# fresh_air_control.net
KiCad netlist of a schematic drawn in EAGLE
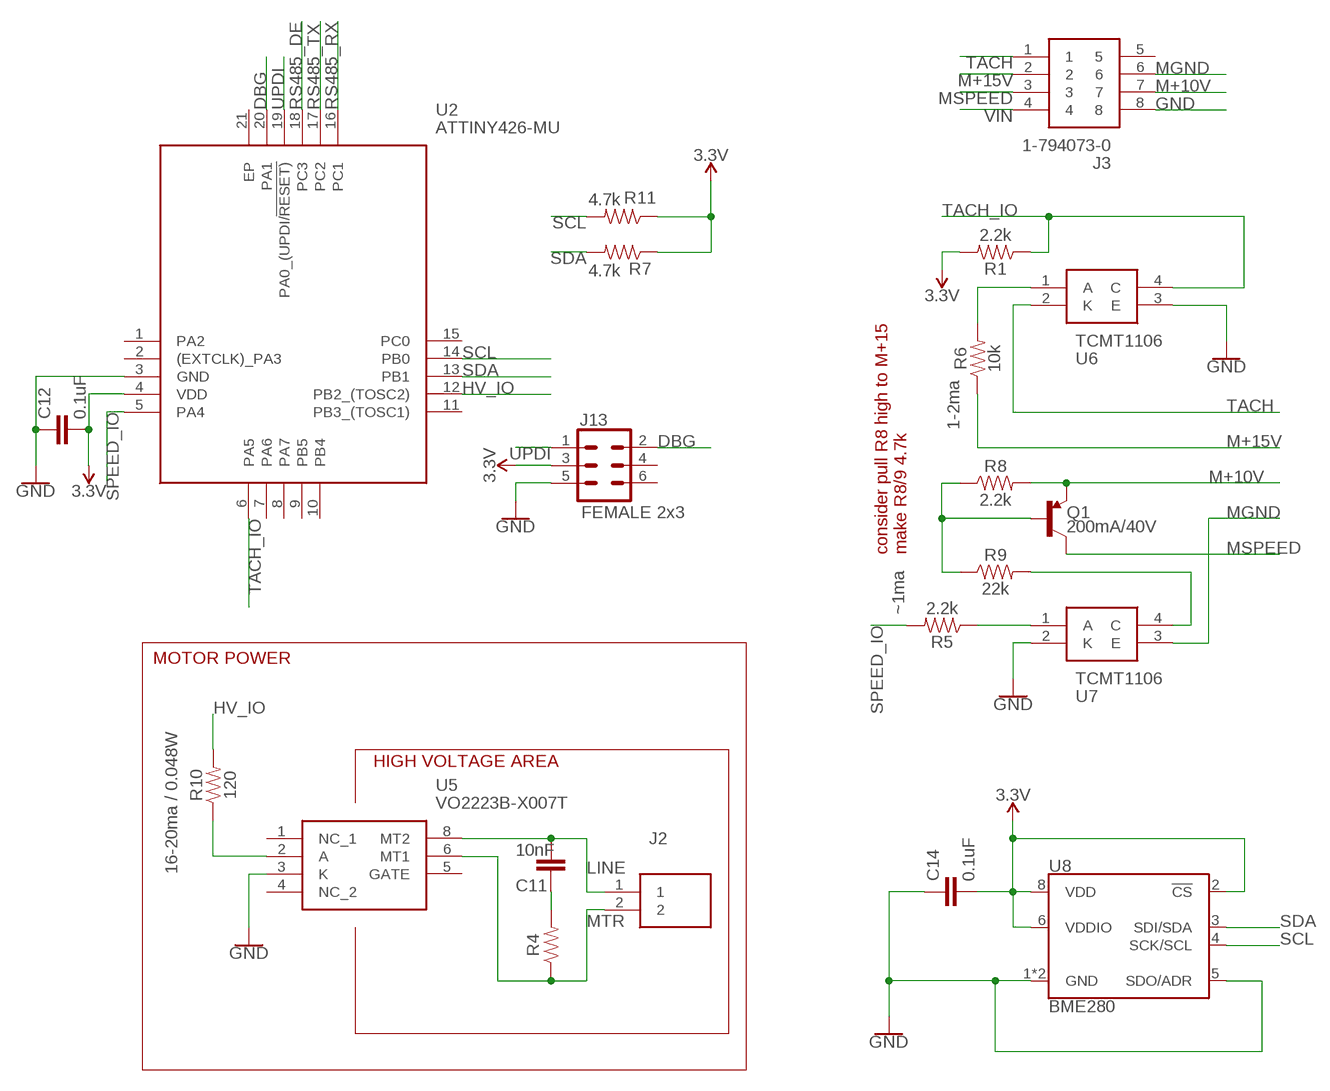
[diagram p0: schematic, sheet 1]
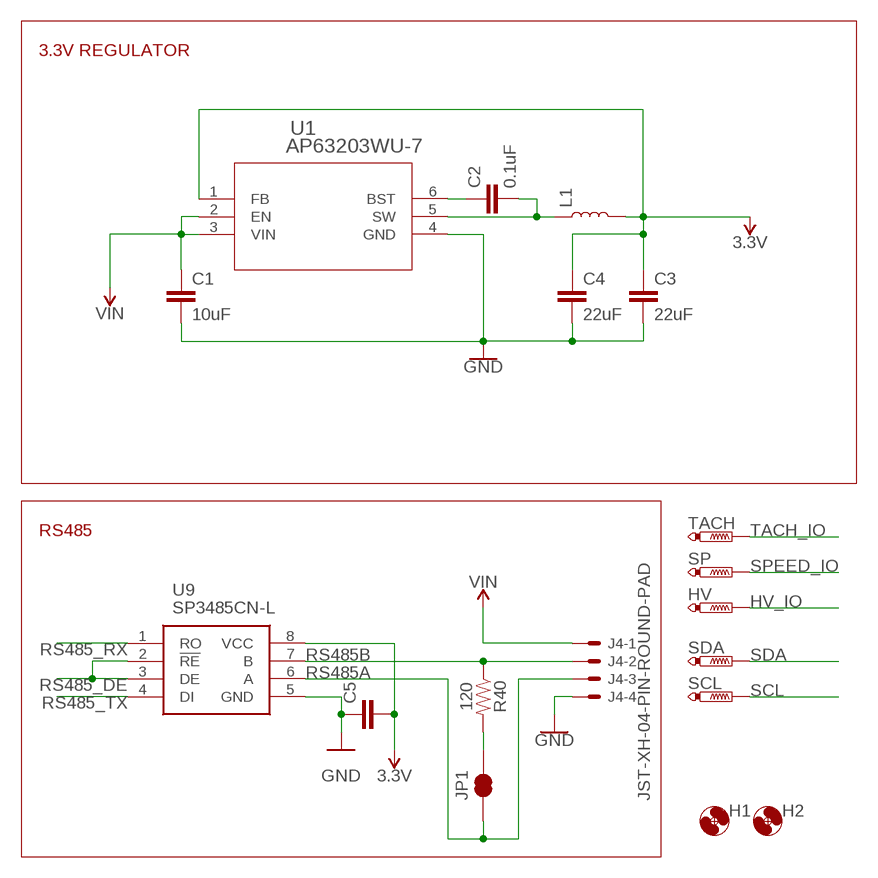
[diagram p1: schematic, sheet 2]

(export (version "E")
  (design (tool "Eeschema 10.0.6"))
  (components
    (comp (ref "C11")
      (value "10nF")
      (footprint "eagle-import:0805")
      (libsource (lib "eagle-import") (part "10NF-0805-400V-20%"))
    )
    (comp (ref "C12")
      (value "0.1uF")
      (footprint "eagle-import:0603")
      (libsource (lib "eagle-import") (part "0.1UF-0603-25V-5%"))
    )
    (comp (ref "C14")
      (value "0.1uF")
      (footprint "eagle-import:0603")
      (libsource (lib "eagle-import") (part "0.1UF-0603-25V-5%"))
    )
    (comp (ref "J2")
      (value "1-770166-0")
      (footprint "eagle-import:17701660")
      (fields (field (name "MOUSER_PART_NUMBER") "571-1-770166-0"))
      (libsource (lib "eagle-import") (part "1-770166-0"))
    )
    (comp (ref "J3")
      (value "1-794073-0")
      (footprint "eagle-import:17940730")
      (fields (field (name "MOUSER_PART_NUMBER") "571-1-794073-0"))
      (libsource (lib "eagle-import") (part "1-794073-0"))
    )
    (comp (ref "J13")
      (value "FEMALE 2x3")
      (footprint "eagle-import:2X3")
      (libsource (lib "eagle-import") (part "CONN_03X2FEMALE"))
    )
    (comp (ref "Q1")
      (value "200mA/40V")
      (footprint "eagle-import:SOT23-3")
      (libsource (lib "eagle-import") (part "TRANS_PNP-PMBT3906|MMBT3906L"))
    )
    (comp (ref "R1")
      (value "2.2k")
      (footprint "eagle-import:0603")
      (libsource (lib "eagle-import") (part "2.2KOHM-0603-1/10W-1%"))
    )
    (comp (ref "R4")
      (value "100")
      (footprint "eagle-import:0805")
      (libsource (lib "eagle-import") (part "100OHM-0805-1/10W-5%-400V"))
    )
    (comp (ref "R5")
      (value "2.2k")
      (footprint "eagle-import:0603")
      (libsource (lib "eagle-import") (part "2.2KOHM-0603-1/10W-1%"))
    )
    (comp (ref "R6")
      (value "10k")
      (footprint "eagle-import:0603")
      (libsource (lib "eagle-import") (part "10KOHM-0603-1/10W-1%"))
    )
    (comp (ref "R7")
      (value "4.7k")
      (footprint "eagle-import:0603")
      (libsource (lib "eagle-import") (part "4.7KOHM-0603-1/10W-1%"))
    )
    (comp (ref "R8")
      (value "2.2k")
      (footprint "eagle-import:0603")
      (libsource (lib "eagle-import") (part "2.2KOHM-0603-1/10W-1%"))
    )
    (comp (ref "R9")
      (value "22k")
      (footprint "eagle-import:0603")
      (libsource (lib "eagle-import") (part "22KOHM-0603-1/10W-1%"))
    )
    (comp (ref "R10")
      (value "120")
      (footprint "eagle-import:0603")
      (libsource (lib "eagle-import") (part "120OHM-0603-1/10W-5%"))
    )
    (comp (ref "R11")
      (value "4.7k")
      (footprint "eagle-import:0603")
      (libsource (lib "eagle-import") (part "4.7KOHM-0603-1/10W-1%"))
    )
    (comp (ref "U2")
      (value "ATTINY426-MU")
      (footprint "eagle-import:QFN40P300X300X90-21N")
      (fields (field (name "MOUSER_PART_NUMBER") "579-ATTINY426-MU"))
      (libsource (lib "eagle-import") (part "ATTINY426-MU"))
    )
    (comp (ref "U5")
      (value "VO2223B-X007T")
      (footprint "eagle-import:VO2223BX007T")
      (fields (field (name "MOUSER_PART_NUMBER") "78-VO2223B-X007T"))
      (libsource (lib "eagle-import") (part "VO2223B-X007T"))
    )
    (comp (ref "U6")
      (value "TCMT1106")
      (footprint "eagle-import:SOIC127P700X230-4N")
      (fields (field (name "MOUSER_PART_NUMBER") "782-TCMT1106"))
      (libsource (lib "eagle-import") (part "TCMT1106"))
    )
    (comp (ref "U7")
      (value "TCMT1106")
      (footprint "eagle-import:SOIC127P700X230-4N")
      (fields (field (name "MOUSER_PART_NUMBER") "782-TCMT1106"))
      (libsource (lib "eagle-import") (part "TCMT1106"))
    )
    (comp (ref "U8")
      (value "BME280")
      (footprint "eagle-import:LGA-8-2.5X2.5")
      (libsource (lib "eagle-import") (part "BME280"))
    )
    (comp (ref "C1")
      (value "10uF")
      (footprint "eagle-import:1206")
      (libsource (lib "eagle-import") (part "10UF-1206-6.3V-20%"))
    )
    (comp (ref "C2")
      (value "0.1uF")
      (footprint "eagle-import:0603")
      (libsource (lib "eagle-import") (part "0.1UF-0603-25V-5%"))
    )
    (comp (ref "C3")
      (value "22uF")
      (footprint "eagle-import:0805")
      (libsource (lib "eagle-import") (part "22UF-0805-6.3V-20%"))
    )
    (comp (ref "C4")
      (value "22uF")
      (footprint "eagle-import:0805")
      (libsource (lib "eagle-import") (part "22UF-0805-6.3V-20%"))
    )
    (comp (ref "C5")
      (value "0.1uF")
      (footprint "eagle-import:0603")
      (libsource (lib "eagle-import") (part "0.1UF-0603-25V-5%"))
    )
    (comp (ref "H1")
      (value "MOUNT-HOLE3.3")
      (footprint "eagle-import:3,3")
      (libsource (lib "eagle-import") (part "MOUNT-HOLE3.3"))
    )
    (comp (ref "H2")
      (value "MOUNT-HOLE3.3")
      (footprint "eagle-import:3,3")
      (libsource (lib "eagle-import") (part "MOUNT-HOLE3.3"))
    )
    (comp (ref "HV")
      (value "PTR1B1,27")
      (footprint "eagle-import:B1,27")
      (libsource (lib "eagle-import") (part "PTR1B1,27"))
    )
    (comp (ref "J4")
      (value "JST-XH-04-PIN-ROUND-PAD")
      (footprint "eagle-import:JST-XH-04-PACKAGE-ROUND-PAD")
      (libsource (lib "eagle-import") (part "JST-XH-04-PIN-ROUND-PAD"))
    )
    (comp (ref "JP1")
      (value "JUMPER-SMT_2_NC_TRACE_NO-SILK")
      (footprint "eagle-import:SMT-JUMPER_2_NC_TRACE_NO-SILK")
      (libsource (lib "eagle-import") (part "JUMPER-SMT_2_NC_TRACE_NO-SILK"))
    )
    (comp (ref "L1")
      (value "4.7μH_SHIELDED_INDUCTOR")
      (footprint "eagle-import:1008(2520)")
      (libsource (lib "eagle-import") (part "4.7μH_SHIELDED_INDUCTOR"))
    )
    (comp (ref "R40")
      (value "120")
      (footprint "eagle-import:0603")
      (libsource (lib "eagle-import") (part "120OHM-0603-1/10W-5%"))
    )
    (comp (ref "SCL")
      (value "PTR1B1,27")
      (footprint "eagle-import:B1,27")
      (libsource (lib "eagle-import") (part "PTR1B1,27"))
    )
    (comp (ref "SDA")
      (value "PTR1B1,27")
      (footprint "eagle-import:B1,27")
      (libsource (lib "eagle-import") (part "PTR1B1,27"))
    )
    (comp (ref "SP")
      (value "PTR1B1,27")
      (footprint "eagle-import:B1,27")
      (libsource (lib "eagle-import") (part "PTR1B1,27"))
    )
    (comp (ref "TACH")
      (value "PTR1B1,27")
      (footprint "eagle-import:B1,27")
      (libsource (lib "eagle-import") (part "PTR1B1,27"))
    )
    (comp (ref "U1")
      (value "AP63203WU-7")
      (footprint "eagle-import:SOIC_05WU-7_DIO")
      (fields (field (name "COPYRIGHT") "Copyright (C) 2023 Ultra Librarian. All rights reserved."))
      (libsource (lib "eagle-import") (part "AP63203WU-7"))
    )
    (comp (ref "U9")
      (value "SP3485CN-L")
      (footprint "eagle-import:SOIC127P600X175-8N")
      (fields (field (name "MOUSER_PART_NUMBER") "701-SP3485CN-L"))
      (libsource (lib "eagle-import") (part "SP3485CN-L"))
    )
  )
  (nets
    (net (code "1") (name "3.3V") (class "Default")
      (node (ref "C12") (pin "2") (pinfunction "2_2") (pintype "passive"))
      (node (ref "C14") (pin "2") (pinfunction "2_2") (pintype "passive"))
      (node (ref "C3") (pin "1") (pinfunction "1_1") (pintype "passive"))
      (node (ref "C4") (pin "1") (pinfunction "1_1") (pintype "passive"))
      (node (ref "C5") (pin "2") (pinfunction "2_2") (pintype "passive"))
      (node (ref "J13") (pin "3") (pinfunction "3_3") (pintype "bidirectional"))
      (node (ref "L1") (pin "2") (pinfunction "2_2") (pintype "passive"))
      (node (ref "R1") (pin "2") (pinfunction "2_2") (pintype "passive"))
      (node (ref "R11") (pin "1") (pinfunction "1_1") (pintype "passive"))
      (node (ref "R7") (pin "1") (pinfunction "1_1") (pintype "passive"))
      (node (ref "U1") (pin "1") (pinfunction "FB_1") (pintype "passive"))
      (node (ref "U2") (pin "4") (pinfunction "VDD_4") (pintype "bidirectional"))
      (node (ref "U8") (pin "2") (pinfunction "~{CS}_2") (pintype "bidirectional"))
      (node (ref "U8") (pin "6") (pinfunction "VDDIO_6") (pintype "bidirectional"))
      (node (ref "U8") (pin "8") (pinfunction "VDD_8") (pintype "bidirectional"))
      (node (ref "U9") (pin "8") (pinfunction "VCC_8") (pintype "bidirectional"))
    )
    (net (code "2") (name "DBG") (class "Default")
      (node (ref "J13") (pin "2") (pinfunction "2_2") (pintype "bidirectional"))
      (node (ref "U2") (pin "20") (pinfunction "PA1_20") (pintype "bidirectional"))
    )
    (net (code "3") (name "GND") (class "Default")
      (node (ref "C1") (pin "2") (pinfunction "2_2") (pintype "passive"))
      (node (ref "C12") (pin "1") (pinfunction "1_1") (pintype "passive"))
      (node (ref "C14") (pin "1") (pinfunction "1_1") (pintype "passive"))
      (node (ref "C3") (pin "2") (pinfunction "2_2") (pintype "passive"))
      (node (ref "C4") (pin "2") (pinfunction "2_2") (pintype "passive"))
      (node (ref "C5") (pin "1") (pinfunction "1_1") (pintype "passive"))
      (node (ref "J13") (pin "5") (pinfunction "5_5") (pintype "bidirectional"))
      (node (ref "J3") (pin "8") (pinfunction "8_8") (pintype "bidirectional"))
      (node (ref "J4") (pin "4") (pinfunction "S_4") (pintype "passive"))
      (node (ref "U1") (pin "4") (pinfunction "GND_4") (pintype "passive"))
      (node (ref "U2") (pin "3") (pinfunction "GND_3") (pintype "bidirectional"))
      (node (ref "U5") (pin "3") (pinfunction "K_3") (pintype "bidirectional"))
      (node (ref "U6") (pin "3") (pinfunction "E_3") (pintype "bidirectional"))
      (node (ref "U7") (pin "2") (pinfunction "K_2") (pintype "bidirectional"))
      (node (ref "U8") (pin "1") (pinfunction "GND_1") (pintype "bidirectional"))
      (node (ref "U8") (pin "5") (pinfunction "SDO/ADR_5") (pintype "bidirectional"))
      (node (ref "U8") (pin "7") (pinfunction "GND_7") (pintype "bidirectional"))
      (node (ref "U9") (pin "5") (pinfunction "GND_5") (pintype "bidirectional"))
    )
    (net (code "4") (name "HV_IO") (class "Default")
      (node (ref "HV") (pin "TP") (pinfunction "TP_TP") (pintype "input"))
      (node (ref "R10") (pin "2") (pinfunction "2_2") (pintype "passive"))
      (node (ref "U2") (pin "12") (pinfunction "PB2_(TOSC2)_12") (pintype "bidirectional"))
    )
    (net (code "5") (name "LINE") (class "Default")
      (node (ref "C11") (pin "1") (pinfunction "1_1") (pintype "passive"))
      (node (ref "J2") (pin "1") (pinfunction "1_1") (pintype "bidirectional"))
      (node (ref "U5") (pin "8") (pinfunction "MT2_8") (pintype "bidirectional"))
    )
    (net (code "6") (name "M+10V") (class "Default")
      (node (ref "J3") (pin "7") (pinfunction "7_7") (pintype "bidirectional"))
      (node (ref "Q1") (pin "2") (pinfunction "E_2") (pintype "passive"))
      (node (ref "R8") (pin "2") (pinfunction "2_2") (pintype "passive"))
    )
    (net (code "7") (name "M+15V") (class "Default")
      (node (ref "J3") (pin "2") (pinfunction "2_2") (pintype "bidirectional"))
      (node (ref "R6") (pin "1") (pinfunction "1_1") (pintype "passive"))
    )
    (net (code "8") (name "MGND") (class "Default")
      (node (ref "J3") (pin "6") (pinfunction "6_6") (pintype "bidirectional"))
      (node (ref "U7") (pin "3") (pinfunction "E_3") (pintype "bidirectional"))
    )
    (net (code "9") (name "MSPEED") (class "Default")
      (node (ref "J3") (pin "3") (pinfunction "3_3") (pintype "bidirectional"))
      (node (ref "Q1") (pin "3") (pinfunction "C_3") (pintype "passive"))
    )
    (net (code "10") (name "MTR") (class "Default")
      (node (ref "J2") (pin "2") (pinfunction "2_2") (pintype "bidirectional"))
      (node (ref "R4") (pin "1") (pinfunction "1_1") (pintype "passive"))
      (node (ref "U5") (pin "6") (pinfunction "MT1_6") (pintype "bidirectional"))
    )
    (net (code "11") (name "Net-(C11-Pad2)") (class "Default")
      (node (ref "C11") (pin "2") (pinfunction "2_2") (pintype "passive"))
      (node (ref "R4") (pin "2") (pinfunction "2_2") (pintype "passive"))
    )
    (net (code "12") (name "Net-(JP1-Pad2)") (class "Default")
      (node (ref "JP1") (pin "2") (pinfunction "2_2") (pintype "passive"))
      (node (ref "R40") (pin "2") (pinfunction "2_2") (pintype "passive"))
    )
    (net (code "13") (name "Net-(Q1-B)") (class "Default")
      (node (ref "Q1") (pin "1") (pinfunction "B_1") (pintype "passive"))
      (node (ref "R8") (pin "1") (pinfunction "1_1") (pintype "passive"))
      (node (ref "R9") (pin "1") (pinfunction "1_1") (pintype "passive"))
    )
    (net (code "14") (name "Net-(U1-BST)") (class "Default")
      (node (ref "C2") (pin "1") (pinfunction "1_1") (pintype "passive"))
      (node (ref "U1") (pin "6") (pinfunction "BST_6") (pintype "passive"))
    )
    (net (code "15") (name "Net-(U1-SW)") (class "Default")
      (node (ref "C2") (pin "2") (pinfunction "2_2") (pintype "passive"))
      (node (ref "L1") (pin "1") (pinfunction "1_1") (pintype "passive"))
      (node (ref "U1") (pin "5") (pinfunction "SW_5") (pintype "passive"))
    )
    (net (code "16") (name "Net-(U5-A)") (class "Default")
      (node (ref "R10") (pin "1") (pinfunction "1_1") (pintype "passive"))
      (node (ref "U5") (pin "2") (pinfunction "A_2") (pintype "bidirectional"))
    )
    (net (code "17") (name "Net-(U6-A)") (class "Default")
      (node (ref "R6") (pin "2") (pinfunction "2_2") (pintype "passive"))
      (node (ref "U6") (pin "1") (pinfunction "A_1") (pintype "bidirectional"))
    )
    (net (code "18") (name "Net-(U7-A)") (class "Default")
      (node (ref "R5") (pin "1") (pinfunction "1_1") (pintype "passive"))
      (node (ref "U7") (pin "1") (pinfunction "A_1") (pintype "bidirectional"))
    )
    (net (code "19") (name "Net-(U7-C)") (class "Default")
      (node (ref "R9") (pin "2") (pinfunction "2_2") (pintype "passive"))
      (node (ref "U7") (pin "4") (pinfunction "C_4") (pintype "bidirectional"))
    )
    (net (code "20") (name "RS485A") (class "Default")
      (node (ref "J4") (pin "3") (pinfunction "S_3") (pintype "passive"))
      (node (ref "JP1") (pin "1") (pinfunction "1_1") (pintype "passive"))
      (node (ref "U9") (pin "6") (pinfunction "A_6") (pintype "bidirectional"))
    )
    (net (code "21") (name "RS485B") (class "Default")
      (node (ref "J4") (pin "2") (pinfunction "S_2") (pintype "passive"))
      (node (ref "R40") (pin "1") (pinfunction "1_1") (pintype "passive"))
      (node (ref "U9") (pin "7") (pinfunction "B_7") (pintype "bidirectional"))
    )
    (net (code "22") (name "RS485_DE") (class "Default")
      (node (ref "U2") (pin "18") (pinfunction "PC3_18") (pintype "bidirectional"))
      (node (ref "U9") (pin "2") (pinfunction "~{RE}_2") (pintype "bidirectional"))
      (node (ref "U9") (pin "3") (pinfunction "DE_3") (pintype "bidirectional"))
    )
    (net (code "23") (name "RS485_RX") (class "Default")
      (node (ref "U2") (pin "16") (pinfunction "PC1_16") (pintype "bidirectional"))
      (node (ref "U9") (pin "1") (pinfunction "RO_1") (pintype "bidirectional"))
    )
    (net (code "24") (name "RS485_TX") (class "Default")
      (node (ref "U2") (pin "17") (pinfunction "PC2_17") (pintype "bidirectional"))
      (node (ref "U9") (pin "4") (pinfunction "DI_4") (pintype "bidirectional"))
    )
    (net (code "25") (name "SCL") (class "Default")
      (node (ref "R11") (pin "2") (pinfunction "2_2") (pintype "passive"))
      (node (ref "SCL") (pin "TP") (pinfunction "TP_TP") (pintype "input"))
      (node (ref "U2") (pin "14") (pinfunction "PB0_14") (pintype "bidirectional"))
      (node (ref "U8") (pin "4") (pinfunction "SCK/SCL_4") (pintype "bidirectional"))
    )
    (net (code "26") (name "SDA") (class "Default")
      (node (ref "R7") (pin "2") (pinfunction "2_2") (pintype "passive"))
      (node (ref "SDA") (pin "TP") (pinfunction "TP_TP") (pintype "input"))
      (node (ref "U2") (pin "13") (pinfunction "PB1_13") (pintype "bidirectional"))
      (node (ref "U8") (pin "3") (pinfunction "SDI/SDA_3") (pintype "bidirectional"))
    )
    (net (code "27") (name "SPEED_IO") (class "Default")
      (node (ref "R5") (pin "2") (pinfunction "2_2") (pintype "passive"))
      (node (ref "SP") (pin "TP") (pinfunction "TP_TP") (pintype "input"))
      (node (ref "U2") (pin "5") (pinfunction "PA4_5") (pintype "bidirectional"))
    )
    (net (code "28") (name "TACH") (class "Default")
      (node (ref "J3") (pin "1") (pinfunction "1_1") (pintype "bidirectional"))
      (node (ref "U6") (pin "2") (pinfunction "K_2") (pintype "bidirectional"))
    )
    (net (code "29") (name "TACH_IO") (class "Default")
      (node (ref "R1") (pin "1") (pinfunction "1_1") (pintype "passive"))
      (node (ref "TACH") (pin "TP") (pinfunction "TP_TP") (pintype "input"))
      (node (ref "U2") (pin "6") (pinfunction "PA5_6") (pintype "bidirectional"))
      (node (ref "U6") (pin "4") (pinfunction "C_4") (pintype "bidirectional"))
    )
    (net (code "30") (name "UPDI") (class "Default")
      (node (ref "J13") (pin "1") (pinfunction "1_1") (pintype "bidirectional"))
      (node (ref "U2") (pin "19") (pinfunction "PA0_(UPDI/~{RESET})_19") (pintype "bidirectional"))
    )
    (net (code "31") (name "VIN") (class "Default")
      (node (ref "C1") (pin "1") (pinfunction "1_1") (pintype "passive"))
      (node (ref "J3") (pin "4") (pinfunction "4_4") (pintype "bidirectional"))
      (node (ref "J4") (pin "1") (pinfunction "S_1") (pintype "passive"))
      (node (ref "U1") (pin "2") (pinfunction "EN_2") (pintype "passive"))
      (node (ref "U1") (pin "3") (pinfunction "VIN_3") (pintype "passive"))
    )
    (net (code "32") (name "unconnected-(J3-Pad5)") (class "Default")
      (node (ref "J3") (pin "5") (pinfunction "5_5") (pintype "bidirectional"))
    )
    (net (code "33") (name "unconnected-(J13-Pad4)") (class "Default")
      (node (ref "J13") (pin "4") (pinfunction "4_4") (pintype "bidirectional"))
    )
    (net (code "34") (name "unconnected-(J13-Pad6)") (class "Default")
      (node (ref "J13") (pin "6") (pinfunction "6_6") (pintype "bidirectional"))
    )
    (net (code "35") (name "unconnected-(U2-(EXTCLK)_PA3-Pad2)") (class "Default")
      (node (ref "U2") (pin "2") (pinfunction "(EXTCLK)_PA3_2") (pintype "bidirectional"))
    )
    (net (code "36") (name "unconnected-(U2-EP-Pad21)") (class "Default")
      (node (ref "U2") (pin "21") (pinfunction "EP_21") (pintype "bidirectional"))
    )
    (net (code "37") (name "unconnected-(U2-PA2-Pad1)") (class "Default")
      (node (ref "U2") (pin "1") (pinfunction "PA2_1") (pintype "bidirectional"))
    )
    (net (code "38") (name "unconnected-(U2-PA6-Pad7)") (class "Default")
      (node (ref "U2") (pin "7") (pinfunction "PA6_7") (pintype "bidirectional"))
    )
    (net (code "39") (name "unconnected-(U2-PA7-Pad8)") (class "Default")
      (node (ref "U2") (pin "8") (pinfunction "PA7_8") (pintype "bidirectional"))
    )
    (net (code "40") (name "unconnected-(U2-PB3_(TOSC1)-Pad11)") (class "Default")
      (node (ref "U2") (pin "11") (pinfunction "PB3_(TOSC1)_11") (pintype "bidirectional"))
    )
    (net (code "41") (name "unconnected-(U2-PB4-Pad10)") (class "Default")
      (node (ref "U2") (pin "10") (pinfunction "PB4_10") (pintype "bidirectional"))
    )
    (net (code "42") (name "unconnected-(U2-PB5-Pad9)") (class "Default")
      (node (ref "U2") (pin "9") (pinfunction "PB5_9") (pintype "bidirectional"))
    )
    (net (code "43") (name "unconnected-(U2-PC0-Pad15)") (class "Default")
      (node (ref "U2") (pin "15") (pinfunction "PC0_15") (pintype "bidirectional"))
    )
    (net (code "44") (name "unconnected-(U5-GATE-Pad5)") (class "Default")
      (node (ref "U5") (pin "5") (pinfunction "GATE_5") (pintype "bidirectional"))
    )
    (net (code "45") (name "unconnected-(U5-NC_1-Pad1)") (class "Default")
      (node (ref "U5") (pin "1") (pinfunction "NC_1_1") (pintype "bidirectional"))
    )
    (net (code "46") (name "unconnected-(U5-NC_2-Pad4)") (class "Default")
      (node (ref "U5") (pin "4") (pinfunction "NC_2_4") (pintype "bidirectional"))
    )
  )
)
